# Active_comm_connector_1_0.net
KiCad netlist of a schematic drawn in EAGLE
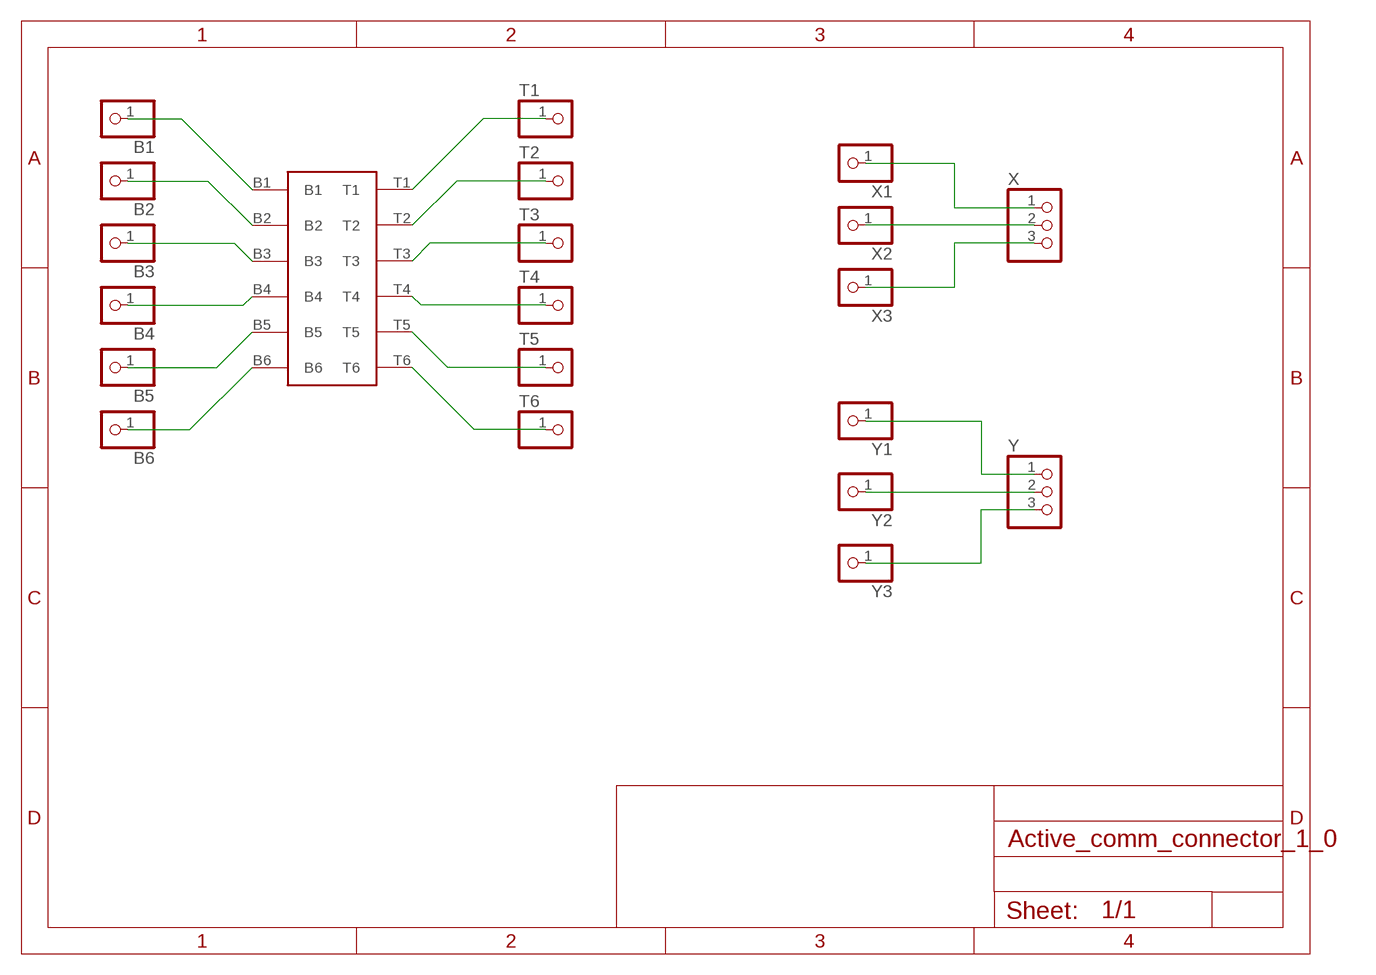
[diagram p0: schematic, sheet 1]

(export (version "E")
  (design (tool "Eeschema 10.0.6"))
  (components
    (comp (ref "B1")
      (value "PINHD-1X1")
      (footprint "eagle-import:1X01")
      (libsource (lib "eagle-import") (part "PINHD-1X1"))
    )
    (comp (ref "B2")
      (value "PINHD-1X1")
      (footprint "eagle-import:1X01")
      (libsource (lib "eagle-import") (part "PINHD-1X1"))
    )
    (comp (ref "B3")
      (value "PINHD-1X1")
      (footprint "eagle-import:1X01")
      (libsource (lib "eagle-import") (part "PINHD-1X1"))
    )
    (comp (ref "B4")
      (value "PINHD-1X1")
      (footprint "eagle-import:1X01")
      (libsource (lib "eagle-import") (part "PINHD-1X1"))
    )
    (comp (ref "B5")
      (value "PINHD-1X1")
      (footprint "eagle-import:1X01")
      (libsource (lib "eagle-import") (part "PINHD-1X1"))
    )
    (comp (ref "B6")
      (value "PINHD-1X1")
      (footprint "eagle-import:1X01")
      (libsource (lib "eagle-import") (part "PINHD-1X1"))
    )
    (comp (ref "PZN-12-VV")
      (value "PZN-12-VV")
      (footprint "eagle-import:OMNETICS_PZN-12-VV")
      (libsource (lib "eagle-import") (part "PZN-12-VV"))
    )
    (comp (ref "T1")
      (value "PINHD-1X1")
      (footprint "eagle-import:1X01")
      (libsource (lib "eagle-import") (part "PINHD-1X1"))
    )
    (comp (ref "T2")
      (value "PINHD-1X1")
      (footprint "eagle-import:1X01")
      (libsource (lib "eagle-import") (part "PINHD-1X1"))
    )
    (comp (ref "T3")
      (value "PINHD-1X1")
      (footprint "eagle-import:1X01")
      (libsource (lib "eagle-import") (part "PINHD-1X1"))
    )
    (comp (ref "T4")
      (value "PINHD-1X1")
      (footprint "eagle-import:1X01")
      (libsource (lib "eagle-import") (part "PINHD-1X1"))
    )
    (comp (ref "T5")
      (value "PINHD-1X1")
      (footprint "eagle-import:1X01")
      (libsource (lib "eagle-import") (part "PINHD-1X1"))
    )
    (comp (ref "T6")
      (value "PINHD-1X1")
      (footprint "eagle-import:1X01")
      (libsource (lib "eagle-import") (part "PINHD-1X1"))
    )
    (comp (ref "X")
      (value "PINHD-1X3")
      (footprint "eagle-import:1X03")
      (libsource (lib "eagle-import") (part "PINHD-1X3"))
    )
    (comp (ref "X1")
      (value "PINHD-1X1")
      (footprint "eagle-import:1X01")
      (libsource (lib "eagle-import") (part "PINHD-1X1"))
    )
    (comp (ref "X2")
      (value "PINHD-1X1")
      (footprint "eagle-import:1X01")
      (libsource (lib "eagle-import") (part "PINHD-1X1"))
    )
    (comp (ref "X3")
      (value "PINHD-1X1")
      (footprint "eagle-import:1X01")
      (libsource (lib "eagle-import") (part "PINHD-1X1"))
    )
    (comp (ref "Y")
      (value "PINHD-1X3")
      (footprint "eagle-import:1X03")
      (libsource (lib "eagle-import") (part "PINHD-1X3"))
    )
    (comp (ref "Y1")
      (value "PINHD-1X1")
      (footprint "eagle-import:1X01")
      (libsource (lib "eagle-import") (part "PINHD-1X1"))
    )
    (comp (ref "Y2")
      (value "PINHD-1X1")
      (footprint "eagle-import:1X01")
      (libsource (lib "eagle-import") (part "PINHD-1X1"))
    )
    (comp (ref "Y3")
      (value "PINHD-1X1")
      (footprint "eagle-import:1X01")
      (libsource (lib "eagle-import") (part "PINHD-1X1"))
    )
  )
  (nets
    (net (code "1") (name "Net-(B1-Pad1)") (class "Default")
      (node (ref "B1") (pin "1") (pinfunction "1_1") (pintype "passive"))
      (node (ref "PZN-12-VV") (pin "B1") (pinfunction "B1_B1") (pintype "bidirectional"))
    )
    (net (code "2") (name "Net-(B2-Pad1)") (class "Default")
      (node (ref "B2") (pin "1") (pinfunction "1_1") (pintype "passive"))
      (node (ref "PZN-12-VV") (pin "B2") (pinfunction "B2_B2") (pintype "bidirectional"))
    )
    (net (code "3") (name "Net-(B3-Pad1)") (class "Default")
      (node (ref "B3") (pin "1") (pinfunction "1_1") (pintype "passive"))
      (node (ref "PZN-12-VV") (pin "B3") (pinfunction "B3_B3") (pintype "bidirectional"))
    )
    (net (code "4") (name "Net-(B4-Pad1)") (class "Default")
      (node (ref "B4") (pin "1") (pinfunction "1_1") (pintype "passive"))
      (node (ref "PZN-12-VV") (pin "B4") (pinfunction "B4_B4") (pintype "bidirectional"))
    )
    (net (code "5") (name "Net-(B5-Pad1)") (class "Default")
      (node (ref "B5") (pin "1") (pinfunction "1_1") (pintype "passive"))
      (node (ref "PZN-12-VV") (pin "B5") (pinfunction "B5_B5") (pintype "bidirectional"))
    )
    (net (code "6") (name "Net-(B6-Pad1)") (class "Default")
      (node (ref "B6") (pin "1") (pinfunction "1_1") (pintype "passive"))
      (node (ref "PZN-12-VV") (pin "B6") (pinfunction "B6_B6") (pintype "bidirectional"))
    )
    (net (code "7") (name "Net-(PZN-12-VV-PadT1)") (class "Default")
      (node (ref "PZN-12-VV") (pin "T1") (pinfunction "T1_T1") (pintype "bidirectional"))
      (node (ref "T1") (pin "1") (pinfunction "1_1") (pintype "passive"))
    )
    (net (code "8") (name "Net-(PZN-12-VV-PadT2)") (class "Default")
      (node (ref "PZN-12-VV") (pin "T2") (pinfunction "T2_T2") (pintype "bidirectional"))
      (node (ref "T2") (pin "1") (pinfunction "1_1") (pintype "passive"))
    )
    (net (code "9") (name "Net-(PZN-12-VV-PadT3)") (class "Default")
      (node (ref "PZN-12-VV") (pin "T3") (pinfunction "T3_T3") (pintype "bidirectional"))
      (node (ref "T3") (pin "1") (pinfunction "1_1") (pintype "passive"))
    )
    (net (code "10") (name "Net-(PZN-12-VV-PadT4)") (class "Default")
      (node (ref "PZN-12-VV") (pin "T4") (pinfunction "T4_T4") (pintype "bidirectional"))
      (node (ref "T4") (pin "1") (pinfunction "1_1") (pintype "passive"))
    )
    (net (code "11") (name "Net-(PZN-12-VV-PadT5)") (class "Default")
      (node (ref "PZN-12-VV") (pin "T5") (pinfunction "T5_T5") (pintype "bidirectional"))
      (node (ref "T5") (pin "1") (pinfunction "1_1") (pintype "passive"))
    )
    (net (code "12") (name "Net-(PZN-12-VV-PadT6)") (class "Default")
      (node (ref "PZN-12-VV") (pin "T6") (pinfunction "T6_T6") (pintype "bidirectional"))
      (node (ref "T6") (pin "1") (pinfunction "1_1") (pintype "passive"))
    )
    (net (code "13") (name "Net-(X-Pad1)") (class "Default")
      (node (ref "X") (pin "1") (pinfunction "1_1") (pintype "passive"))
      (node (ref "X1") (pin "1") (pinfunction "1_1") (pintype "passive"))
    )
    (net (code "14") (name "Net-(X-Pad2)") (class "Default")
      (node (ref "X") (pin "2") (pinfunction "2_2") (pintype "passive"))
      (node (ref "X2") (pin "1") (pinfunction "1_1") (pintype "passive"))
    )
    (net (code "15") (name "Net-(X-Pad3)") (class "Default")
      (node (ref "X") (pin "3") (pinfunction "3_3") (pintype "passive"))
      (node (ref "X3") (pin "1") (pinfunction "1_1") (pintype "passive"))
    )
    (net (code "16") (name "Net-(Y-Pad1)") (class "Default")
      (node (ref "Y") (pin "1") (pinfunction "1_1") (pintype "passive"))
      (node (ref "Y1") (pin "1") (pinfunction "1_1") (pintype "passive"))
    )
    (net (code "17") (name "Net-(Y-Pad2)") (class "Default")
      (node (ref "Y") (pin "2") (pinfunction "2_2") (pintype "passive"))
      (node (ref "Y2") (pin "1") (pinfunction "1_1") (pintype "passive"))
    )
    (net (code "18") (name "Net-(Y-Pad3)") (class "Default")
      (node (ref "Y") (pin "3") (pinfunction "3_3") (pintype "passive"))
      (node (ref "Y3") (pin "1") (pinfunction "1_1") (pintype "passive"))
    )
  )
)
